# SHDN-CURRENT-S13-V00-ShutdownRelay.net
KiCad netlist of a schematic drawn in Altium Designer
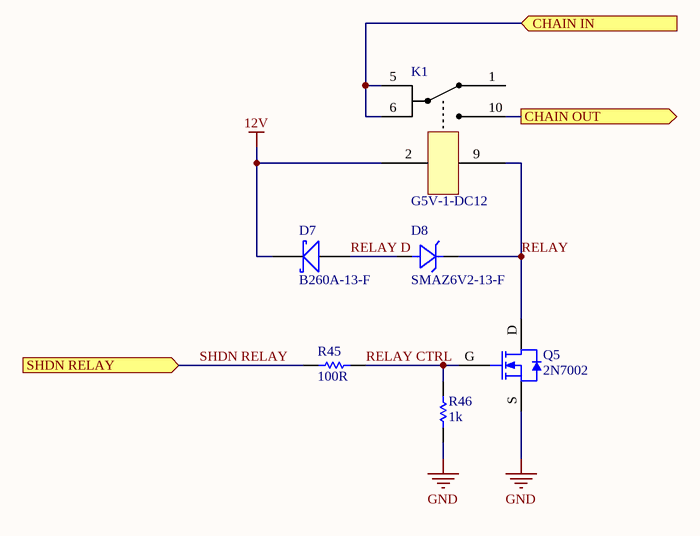
[diagram p0: SHDN-CURRENT-S13-V00-ShutdownRelay.SchDoc]

(export (version "E")
  (design (tool "Eeschema 10.0.6"))
  (components
    (comp (ref "D7")
      (value "B260A-13-F")
      (footprint "SMA")
      (description "Diode, Schottky Barrier Rectifier, 60 V, 2 A, B260A-13-F")
      (libsource (lib "QUTMS_DiodeLibrary") (part "B260A-13-F"))
    )
    (comp (ref "D8")
      (value "SMAZ6V2-13-F")
      (footprint "SMA")
      (description "Zener Diode 6.2V 1W ±5% Surface Mount SMA")
      (fields (field (name "MANUFACTURER") "Generic") (field (name "MPN") "5V6 500mW SMA"))
      (libsource (lib "QUTMS_DiodeLibrary") (part "SMAZ6V2-13-F"))
    )
    (comp (ref "K1")
      (value "G5V-1-DC12")
      (footprint "G5V-1")
      (description "General Purpose Relay SPDT (1 Form C) Through Hole, 12V, 2A")
      (libsource (lib "QUTMS_RelayLibrary") (part "G5V-1-DC12"))
    )
    (comp (ref "Q5")
      (value "2N7002")
      (footprint "SOT23-3")
      (libsource (lib "QUTMS_MOSFETLibrary") (part "2N7002"))
    )
    (comp (ref "R45")
      (value "100R")
      (footprint "Res_ThinFilm_0603")
      (description "Resistor, SMD, 100R, 0.1W, 5%, 0603")
      (libsource (lib "StandardResistors") (part "100R 5%, 0603"))
    )
    (comp (ref "R46")
      (value "1k")
      (footprint "Res_ThinFilm_0603")
      (description "Resistor, SMD, 1k, 0.1W, 5%, 0603")
      (libsource (lib "StandardResistors") (part "1k 5% 0603"))
    )
  )
  (nets
    (net (code "1") (name "/CHAIN IN") (class "Default")
      (node (ref "K1") (pin "5") (pinfunction "5_5") (pintype "passive"))
      (node (ref "K1") (pin "6") (pinfunction "6_6") (pintype "passive"))
    )
    (net (code "2") (name "/CHAIN OUT") (class "Default")
      (node (ref "K1") (pin "10") (pinfunction "10_10") (pintype "passive"))
    )
    (net (code "3") (name "/RELAY") (class "Default")
      (node (ref "D8") (pin "K") (pinfunction "Cathode_K") (pintype "passive"))
      (node (ref "K1") (pin "9") (pinfunction "9_9") (pintype "passive"))
      (node (ref "Q5") (pin "D") (pinfunction "D_D") (pintype "passive"))
    )
    (net (code "4") (name "/RELAY CTRL") (class "Default")
      (node (ref "Q5") (pin "G") (pinfunction "G_G") (pintype "passive"))
      (node (ref "R45") (pin "2") (pinfunction "2_2") (pintype "passive"))
      (node (ref "R46") (pin "2") (pinfunction "2_2") (pintype "passive"))
    )
    (net (code "5") (name "/RELAY D") (class "Default")
      (node (ref "D7") (pin "A") (pinfunction "A_A") (pintype "passive"))
      (node (ref "D8") (pin "A") (pinfunction "Anode_A") (pintype "passive"))
    )
    (net (code "6") (name "/SHDN RELAY") (class "Default")
      (node (ref "R45") (pin "1") (pinfunction "1_1") (pintype "passive"))
    )
    (net (code "7") (name "12V") (class "Default")
      (node (ref "D7") (pin "K") (pinfunction "K_K") (pintype "passive"))
      (node (ref "K1") (pin "2") (pinfunction "2_2") (pintype "passive"))
    )
    (net (code "8") (name "GND") (class "Default")
      (node (ref "Q5") (pin "S") (pinfunction "S_S") (pintype "passive"))
      (node (ref "R46") (pin "1") (pinfunction "1_1") (pintype "passive"))
    )
    (net (code "9") (name "unconnected-(K1-Pad1)") (class "Default")
      (node (ref "K1") (pin "1") (pinfunction "1_1") (pintype "passive"))
    )
  )
)
